# 2_LDO.net
KiCad netlist of a schematic drawn in Altium Designer
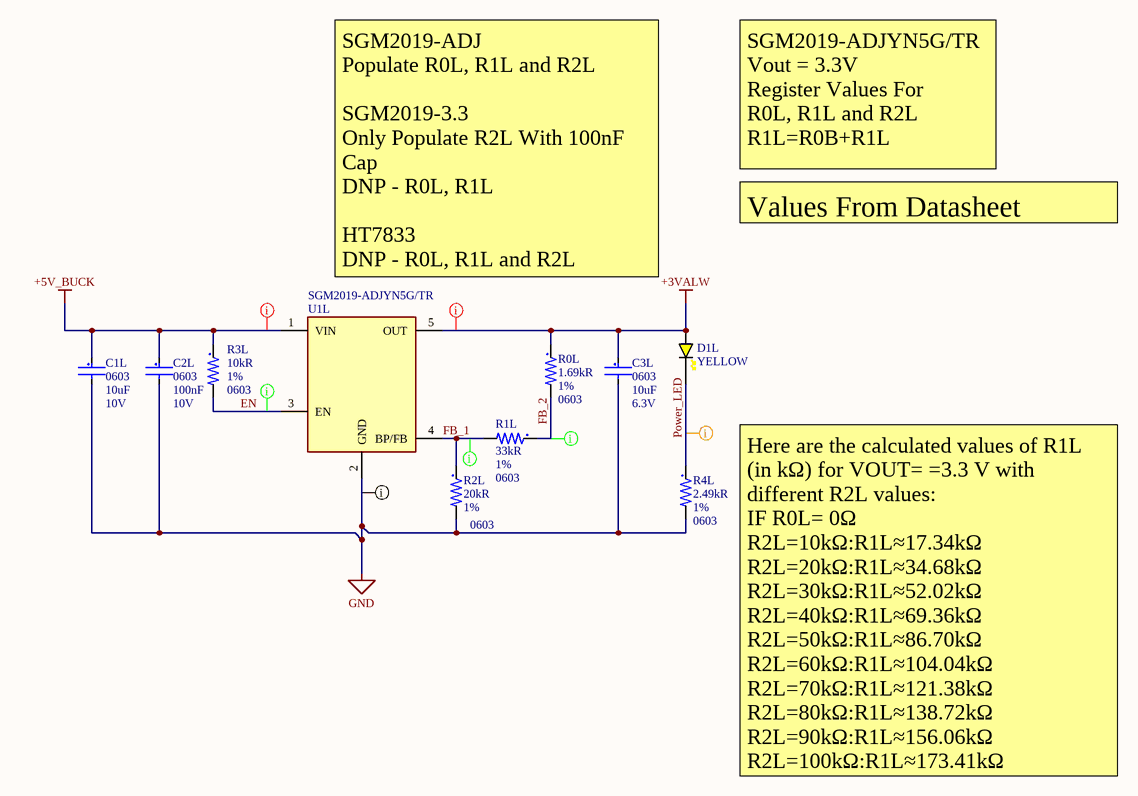
[diagram p0: 2_LDO.SchDoc]

(export (version "E")
  (design (tool "Eeschema 10.0.6"))
  (components
    (comp (ref "C1L")
      (value "10uF")
      (footprint "C0603-IPC_C_No_Silk")
      (description "Multilayer Ceramic Capacitor, 10 uF, 10 V, ± 10%, X5R, 0603 [1608 Metric]")
      (fields
        (field (name "MANUFACTURER") "TDK")
        (field (name "MANUFACTURER PART NUMBER") "C1608X5R1A106K080AC")
        (field (name "CASE/PACKAGE") "0603")
        (field (name "VOLTAGE RATING") "10V")
      )
      (libsource (lib "Lib_Capacitor_0603") (part "10uF_10V"))
    )
    (comp (ref "C2L")
      (value "100nF")
      (footprint "C0603-IPC_C_No_Silk")
      (description "Multilayer Ceramic Capacitor, 0.1 uF, 10 V, ± 10%, X7R, 0603 [1608 Metric]")
      (fields
        (field (name "MANUFACTURER") "KEMET")
        (field (name "MANUFACTURER PART NUMBER") "C0603C104K8RACTU")
        (field (name "CASE/PACKAGE") "0603")
        (field (name "VOLTAGE RATING") "10V")
      )
      (libsource (lib "Lib_Capacitor_0603") (part "100nF_10V"))
    )
    (comp (ref "C3L")
      (value "10uF")
      (footprint "C0603-IPC_C_No_Silk")
      (description "Multilayer Ceramic Capacitor, 10 uF, 6.3 V, ± 10%, X5R, 0603 [1608 Metric]")
      (fields
        (field (name "MANUFACTURER") "Samsung")
        (field (name "MANUFACTURER PART NUMBER") "CL10A106KQ8NNNC")
        (field (name "CASE/PACKAGE") "0603")
        (field (name "VOLTAGE RATING") "6.3V")
      )
      (libsource (lib "Lib_Capacitor_0603") (part "10uF_6.3V"))
    )
    (comp (ref "D1L")
      (value "YELLOW")
      (footprint "LED_0603_YELLOW")
      (description "LED 0603 YELLOW SMD")
      (libsource (lib "Lib_LED") (part "LED_0603_YELLOW"))
    )
    (comp (ref "R0L")
      (value "1.69kR")
      (footprint "R0603-MFG")
      (description "Surface Mount Thick Film Chip Resistor 0603 Case 1.69K Ohms 1% Tolerance 100 PPM")
      (fields
        (field (name "MANUFACTURER") "Rohm")
        (field (name "MANUFACTURER PART NUMBER") "MCR03EZPFX1691")
        (field (name "TOLERANCE") "1%")
        (field (name "CASE/PACKAGE") "0603")
      )
      (libsource (lib "Lib_Register_0603") (part "1.69K"))
    )
    (comp (ref "R1L")
      (value "33kR")
      (footprint "R0603-MFG")
      (description "Res Thick Film 0603 33K Ohm 1% 0.1W(1/10W) ±100ppm/C Pad SMD Automotive T/R")
      (fields
        (field (name "MANUFACTURER") "Panasonic")
        (field (name "MANUFACTURER PART NUMBER") "ERJ-3EKF3302V")
        (field (name "TOLERANCE") "1%")
        (field (name "CASE/PACKAGE") "0603")
      )
      (libsource (lib "Lib_Register_0603") (part "33K"))
    )
    (comp (ref "R2L")
      (value "20kR")
      (footprint "R0603-MFG")
      (description "SMD Chip Resistor, 20 kOhm, ± 1%, 100 mW, 0603 [1608 Metric], Thick Film, General Purpose")
      (fields
        (field (name "MANUFACTURER") "Bourns")
        (field (name "MANUFACTURER PART NUMBER") "CR0603-FX-2002ELF")
        (field (name "TOLERANCE") "1%")
        (field (name "CASE/PACKAGE") "0603")
      )
      (libsource (lib "Lib_Register_0603") (part "20K"))
    )
    (comp (ref "R3L")
      (value "10kR")
      (footprint "R0603-MFG")
      (description "SMD Chip Resistor, 10 kOhm, ± 1%, 100 mW, 0603 [1608 Metric], Thick Film, General Purpose")
      (fields
        (field (name "MANUFACTURER") "Yageo")
        (field (name "MANUFACTURER PART NUMBER") "RC0603FR-0710KL")
        (field (name "TOLERANCE") "1%")
        (field (name "CASE/PACKAGE") "0603")
      )
      (libsource (lib "Lib_Register_0603") (part "10K"))
    )
    (comp (ref "R4L")
      (value "2.49kR")
      (footprint "R0603-MFG")
      (description "Res Thick Film 0603 2.49K Ohm 1% 1/10W ±100ppm/°C Molded SMD SMD Paper T/R")
      (fields
        (field (name "MANUFACTURER") "Rohm")
        (field (name "MANUFACTURER PART NUMBER") "MCR03EZPFX2491")
        (field (name "TOLERANCE") "1%")
        (field (name "CASE/PACKAGE") "0603")
      )
      (libsource (lib "Lib_Register_0603") (part "2.49K"))
    )
    (comp (ref "U1L")
      (value "SGM2019-ADJYN5G/TR")
      (footprint "TSOT-23-5-IPC-A")
      (description "LDO U-Reg Adj 0, 3A SOT23-5")
      (fields (field (name "MANUFACTURER") "SG Micro"))
      (libsource (lib "Lib_LDO") (part "SGM2019-ADJYN5G/TR"))
    )
  )
  (nets
    (net (code "1") (name "+3VALW") (class "Default")
      (node (ref "C3L") (pin "1") (pinfunction "1_1") (pintype "passive"))
      (node (ref "D1L") (pin "2") (pinfunction "A_2") (pintype "passive"))
      (node (ref "R0L") (pin "1") (pinfunction "1_1") (pintype "passive"))
      (node (ref "U1L") (pin "5") (pinfunction "OUT_5") (pintype "power_in"))
    )
    (net (code "2") (name "+5V_BUCK") (class "Default")
      (node (ref "C1L") (pin "1") (pinfunction "1_1") (pintype "passive"))
      (node (ref "C2L") (pin "1") (pinfunction "1_1") (pintype "passive"))
      (node (ref "R3L") (pin "1") (pinfunction "1_1") (pintype "passive"))
      (node (ref "U1L") (pin "1") (pinfunction "VIN_1") (pintype "power_in"))
    )
    (net (code "3") (name "/EN") (class "Default")
      (node (ref "R3L") (pin "2") (pinfunction "2_2") (pintype "passive"))
      (node (ref "U1L") (pin "3") (pinfunction "EN_3") (pintype "passive"))
    )
    (net (code "4") (name "/FB_1") (class "Default")
      (node (ref "R1L") (pin "2") (pinfunction "2_2") (pintype "passive"))
      (node (ref "R2L") (pin "1") (pinfunction "1_1") (pintype "passive"))
      (node (ref "U1L") (pin "4") (pinfunction "BP/FB_4") (pintype "passive"))
    )
    (net (code "5") (name "/FB_2") (class "Default")
      (node (ref "R0L") (pin "2") (pinfunction "2_2") (pintype "passive"))
      (node (ref "R1L") (pin "1") (pinfunction "1_1") (pintype "passive"))
    )
    (net (code "6") (name "/Power_LED") (class "Default")
      (node (ref "D1L") (pin "1") (pinfunction "K_1") (pintype "passive"))
      (node (ref "R4L") (pin "1") (pinfunction "1_1") (pintype "passive"))
    )
    (net (code "7") (name "GND") (class "Default")
      (node (ref "C1L") (pin "2") (pinfunction "2_2") (pintype "passive"))
      (node (ref "C2L") (pin "2") (pinfunction "2_2") (pintype "passive"))
      (node (ref "C3L") (pin "2") (pinfunction "2_2") (pintype "passive"))
      (node (ref "R2L") (pin "2") (pinfunction "2_2") (pintype "passive"))
      (node (ref "R4L") (pin "2") (pinfunction "2_2") (pintype "passive"))
      (node (ref "U1L") (pin "2") (pinfunction "GND_2") (pintype "power_in"))
    )
  )
)
